# LCD.net
KiCad netlist of a schematic drawn in Altium Designer
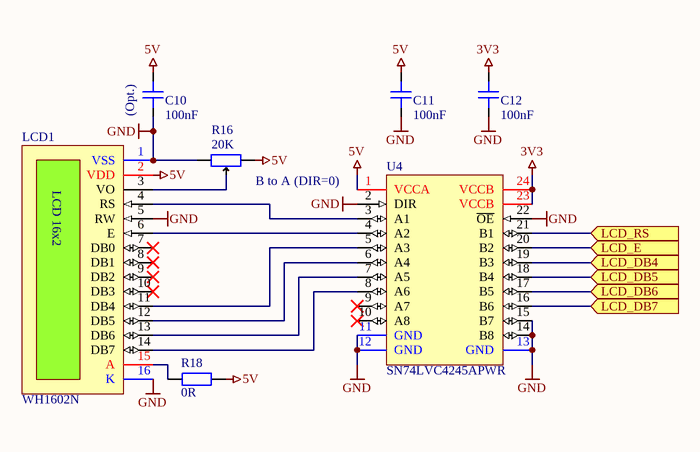
[diagram p0: LCD.SchDoc]

(export (version "E")
  (design (tool "Eeschema 10.0.6"))
  (components
    (comp (ref "C10")
      (value "100nF")
      (footprint "0603C_RF_M")
      (description "Capacitor")
      (fields (field (name "TOLERANCE") "?") (field (name "MANUFACTURER") "Generic Brand"))
      (libsource (lib "AG.Generic") (part "C"))
    )
    (comp (ref "C11")
      (value "100nF")
      (footprint "0603C_RF_M")
      (description "Capacitor")
      (fields (field (name "TOLERANCE") "?") (field (name "MANUFACTURER") "Generic Brand"))
      (libsource (lib "AG.Generic") (part "C"))
    )
    (comp (ref "C12")
      (value "100nF")
      (footprint "0603C_RF_M")
      (description "Capacitor")
      (fields (field (name "TOLERANCE") "?") (field (name "MANUFACTURER") "Generic Brand"))
      (libsource (lib "AG.Generic") (part "C"))
    )
    (comp (ref "LCD1")
      (value "WH1602N")
      (footprint "PINHDR-16P1-2.54")
      (description "Dot Matrix Character LCD Module 16x2")
      (fields (field (name "MANUFACTURER") "Winstar") (field (name "MANUFACTURER PART NO") "WH1602B-YYH-CTK"))
      (libsource (lib "AG.Modules") (part "WH1602N"))
    )
    (comp (ref "R16")
      (value "20K")
      (footprint "BOURNS_3362P")
      (description "Generic Potentiometer / Variable Resistor")
      (fields (field (name "TOLERANCE") "1%"))
      (libsource (lib "AG.Generic") (part "POT"))
    )
    (comp (ref "R18")
      (value "0R")
      (footprint "0603R_RF_M")
      (description "Resistor")
      (fields (field (name "TOLERANCE") "?") (field (name "MANUFACTURER") "Generic Brand"))
      (libsource (lib "AG.Generic") (part "R"))
    )
    (comp (ref "U4")
      (value "SN74LVC4245APWR")
      (footprint "TI_TSSOP-24")
      (description "Octal Bus Transceiver And 3.3-V To 5-V Shifter With 3-State Outputs")
      (fields (field (name "MANUFACTURER") "Texas Instruments"))
      (libsource (lib "AG.IC") (part "SN74LVC4245APWR"))
    )
  )
  (nets
    (net (code "1") (name "/LCD_DB4") (class "Default")
      (node (ref "U4") (pin "19") (pinfunction "B3_19") (pintype "bidirectional"))
    )
    (net (code "2") (name "/LCD_DB5") (class "Default")
      (node (ref "U4") (pin "18") (pinfunction "B4_18") (pintype "bidirectional"))
    )
    (net (code "3") (name "/LCD_DB6") (class "Default")
      (node (ref "U4") (pin "17") (pinfunction "B5_17") (pintype "bidirectional"))
    )
    (net (code "4") (name "/LCD_DB7") (class "Default")
      (node (ref "U4") (pin "16") (pinfunction "B6_16") (pintype "bidirectional"))
    )
    (net (code "5") (name "/LCD_E") (class "Default")
      (node (ref "U4") (pin "20") (pinfunction "B2_20") (pintype "bidirectional"))
    )
    (net (code "6") (name "/LCD_RS") (class "Default")
      (node (ref "U4") (pin "21") (pinfunction "B1_21") (pintype "bidirectional"))
    )
    (net (code "7") (name "3V3") (class "Default")
      (node (ref "C12") (pin "2") (pinfunction "2_2") (pintype "passive"))
      (node (ref "U4") (pin "23") (pinfunction "VCCB_23") (pintype "power_in"))
      (node (ref "U4") (pin "24") (pinfunction "VCCB_24") (pintype "power_in"))
    )
    (net (code "8") (name "5V") (class "Default")
      (node (ref "C10") (pin "2") (pinfunction "2_2") (pintype "passive"))
      (node (ref "C11") (pin "2") (pinfunction "2_2") (pintype "passive"))
      (node (ref "LCD1") (pin "2") (pinfunction "VDD_2") (pintype "power_in"))
      (node (ref "R16") (pin "1") (pintype "passive"))
      (node (ref "R18") (pin "1") (pintype "passive"))
      (node (ref "U4") (pin "1") (pinfunction "VCCA_1") (pintype "power_in"))
    )
    (net (code "9") (name "GND") (class "Default")
      (node (ref "C10") (pin "1") (pinfunction "1_1") (pintype "passive"))
      (node (ref "C11") (pin "1") (pinfunction "1_1") (pintype "passive"))
      (node (ref "C12") (pin "1") (pinfunction "1_1") (pintype "passive"))
      (node (ref "LCD1") (pin "1") (pinfunction "VSS_1") (pintype "power_in"))
      (node (ref "LCD1") (pin "16") (pinfunction "K_16") (pintype "power_in"))
      (node (ref "LCD1") (pin "5") (pinfunction "RW_5") (pintype "input"))
      (node (ref "R16") (pin "2") (pintype "passive"))
      (node (ref "U4") (pin "11") (pinfunction "GND_11") (pintype "power_in"))
      (node (ref "U4") (pin "12") (pinfunction "GND_12") (pintype "power_in"))
      (node (ref "U4") (pin "13") (pinfunction "GND_13") (pintype "power_in"))
      (node (ref "U4") (pin "14") (pinfunction "B8_14") (pintype "bidirectional"))
      (node (ref "U4") (pin "15") (pinfunction "B7_15") (pintype "bidirectional"))
      (node (ref "U4") (pin "2") (pinfunction "DIR_2") (pintype "input"))
      (node (ref "U4") (pin "22") (pinfunction "~{OE}_22") (pintype "input"))
    )
    (net (code "10") (name "Net-(LCD1-A)") (class "Default")
      (node (ref "LCD1") (pin "15") (pinfunction "A_15") (pintype "power_in"))
      (node (ref "R18") (pin "2") (pintype "passive"))
    )
    (net (code "11") (name "Net-(LCD1-DB4)") (class "Default")
      (node (ref "LCD1") (pin "11") (pinfunction "DB4_11") (pintype "bidirectional"))
      (node (ref "U4") (pin "5") (pinfunction "A3_5") (pintype "bidirectional"))
    )
    (net (code "12") (name "Net-(LCD1-DB5)") (class "Default")
      (node (ref "LCD1") (pin "12") (pinfunction "DB5_12") (pintype "bidirectional"))
      (node (ref "U4") (pin "6") (pinfunction "A4_6") (pintype "bidirectional"))
    )
    (net (code "13") (name "Net-(LCD1-DB6)") (class "Default")
      (node (ref "LCD1") (pin "13") (pinfunction "DB6_13") (pintype "bidirectional"))
      (node (ref "U4") (pin "7") (pinfunction "A5_7") (pintype "bidirectional"))
    )
    (net (code "14") (name "Net-(LCD1-DB7)") (class "Default")
      (node (ref "LCD1") (pin "14") (pinfunction "DB7_14") (pintype "bidirectional"))
      (node (ref "U4") (pin "8") (pinfunction "A6_8") (pintype "bidirectional"))
    )
    (net (code "15") (name "Net-(LCD1-E)") (class "Default")
      (node (ref "LCD1") (pin "6") (pinfunction "E_6") (pintype "input"))
      (node (ref "U4") (pin "4") (pinfunction "A2_4") (pintype "bidirectional"))
    )
    (net (code "16") (name "Net-(LCD1-RS)") (class "Default")
      (node (ref "LCD1") (pin "4") (pinfunction "RS_4") (pintype "input"))
      (node (ref "U4") (pin "3") (pinfunction "A1_3") (pintype "bidirectional"))
    )
    (net (code "17") (name "Net-(LCD1-VO)") (class "Default")
      (node (ref "LCD1") (pin "3") (pinfunction "VO_3") (pintype "power_in"))
      (node (ref "R16") (pin "3") (pintype "passive"))
    )
    (net (code "18") (name "unconnected-(LCD1-DB0-Pad7)") (class "Default")
      (node (ref "LCD1") (pin "7") (pinfunction "DB0_7") (pintype "bidirectional+no_connect"))
    )
    (net (code "19") (name "unconnected-(LCD1-DB1-Pad8)") (class "Default")
      (node (ref "LCD1") (pin "8") (pinfunction "DB1_8") (pintype "bidirectional+no_connect"))
    )
    (net (code "20") (name "unconnected-(LCD1-DB2-Pad9)") (class "Default")
      (node (ref "LCD1") (pin "9") (pinfunction "DB2_9") (pintype "bidirectional+no_connect"))
    )
    (net (code "21") (name "unconnected-(LCD1-DB3-Pad10)") (class "Default")
      (node (ref "LCD1") (pin "10") (pinfunction "DB3_10") (pintype "bidirectional+no_connect"))
    )
    (net (code "22") (name "unconnected-(U4-A7-Pad9)") (class "Default")
      (node (ref "U4") (pin "9") (pinfunction "A7_9") (pintype "bidirectional+no_connect"))
    )
    (net (code "23") (name "unconnected-(U4-A8-Pad10)") (class "Default")
      (node (ref "U4") (pin "10") (pinfunction "A8_10") (pintype "bidirectional+no_connect"))
    )
  )
)
